# MCU.net
KiCad netlist of a schematic drawn in Altium Designer
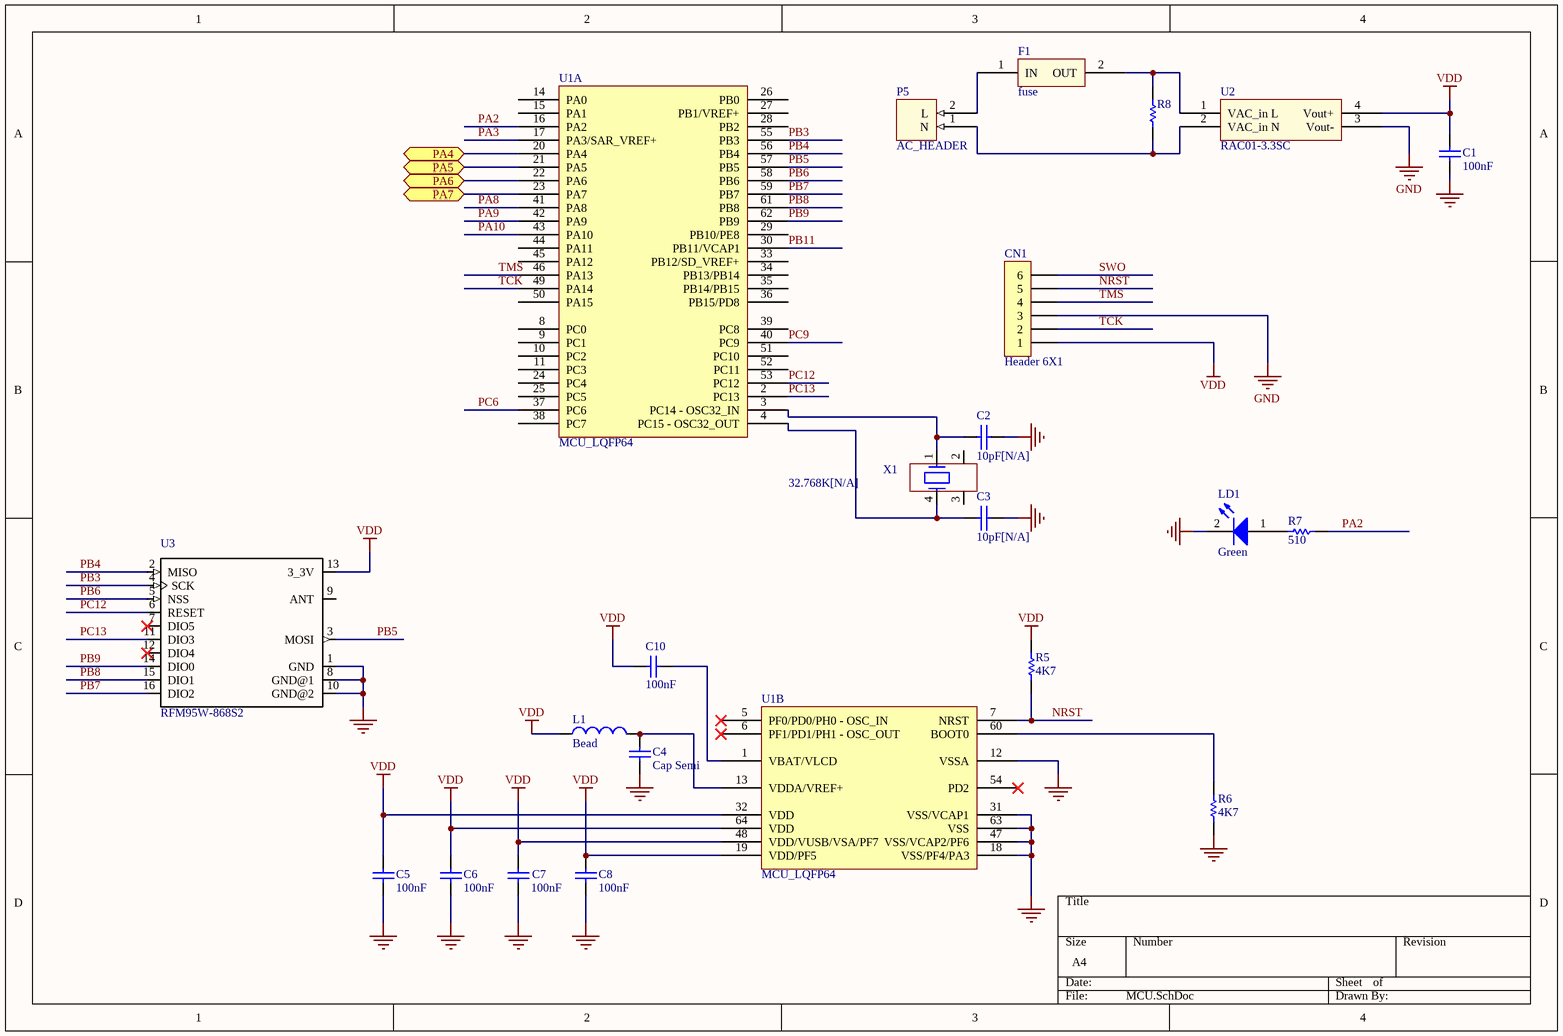
[diagram p0: MCU.SchDoc]

(export (version "E")
  (design (tool "Eeschema 10.0.6"))
  (components
    (comp (ref "C1")
      (value "100nF")
      (footprint "0603C")
      (description "Capacitor")
      (fields (field (name "MANUFACTURER") "AVX Corporation") (field (name "PUBLISHER") "Altium Limited"))
      (libsource (lib "Miscellaneous Devices") (part "Cap"))
    )
    (comp (ref "C2")
      (value "10pF[N/A]")
      (footprint "0603C")
      (description "Capacitor")
      (fields (field (name "MANUFACTURER") "Murata Electronics North America"))
      (libsource (lib "MB1136") (part "CAP"))
    )
    (comp (ref "C3")
      (value "10pF[N/A]")
      (footprint "0603C")
      (description "Capacitor")
      (fields (field (name "MANUFACTURER") "Murata Electronics North America"))
      (libsource (lib "*") (part "CAP"))
    )
    (comp (ref "C4")
      (value "Cap Semi")
      (footprint "1608[0603]")
      (description "Capacitor (Semiconductor SIM Model)")
      (fields (field (name "MANUFACTURER") "TDK") (field (name "PUBLISHER") "Altium Limited"))
      (libsource (lib "Miscellaneous Devices") (part "Cap Semi"))
    )
    (comp (ref "C5")
      (value "100nF")
      (footprint "0603C")
      (description "Capacitor")
      (fields (field (name "MANUFACTURER") "TDK") (field (name "PUBLISHER") "Altium Limited"))
      (libsource (lib "Miscellaneous Devices") (part "Cap"))
    )
    (comp (ref "C6")
      (value "100nF")
      (footprint "0603C")
      (description "Capacitor")
      (fields (field (name "MANUFACTURER") "TDK") (field (name "PUBLISHER") "Altium Limited"))
      (libsource (lib "Miscellaneous Devices") (part "Cap"))
    )
    (comp (ref "C7")
      (value "100nF")
      (footprint "0603C")
      (description "Capacitor")
      (fields (field (name "MANUFACTURER") "TDK") (field (name "PUBLISHER") "Altium Limited"))
      (libsource (lib "Miscellaneous Devices") (part "Cap"))
    )
    (comp (ref "C8")
      (value "100nF")
      (footprint "0603C")
      (description "Capacitor")
      (fields (field (name "MANUFACTURER") "TDK") (field (name "PUBLISHER") "Altium Limited"))
      (libsource (lib "Miscellaneous Devices") (part "Cap"))
    )
    (comp (ref "C10")
      (value "100nF")
      (footprint "0603C")
      (description "Capacitor")
      (fields (field (name "MANUFACTURER") "AVX Corporation") (field (name "PUBLISHER") "Altium Limited"))
      (libsource (lib "Miscellaneous Devices") (part "Cap"))
    )
    (comp (ref "CN1")
      (value "Header 6X1")
      (footprint "1*6P")
      (description "Header, 6-Pin, Single row")
      (fields (field (name "MANUFACTURER") "Molex") (field (name "PUBLISHER") "Altium Limited"))
      (libsource (lib "MB1136") (part "Header 6X1"))
    )
    (comp (ref "F1")
      (value "fuse")
      (footprint "fuse")
      (description "240VAC 1A")
      (fields (field (name "MANUFACTURER") "Bel Fuse Inc."))
      (libsource (lib "seeds") (part "fuse"))
    )
    (comp (ref "L1")
      (value "Bead")
      (footprint "INDC1608L")
      (description "Inductor")
      (fields (field (name "MANUFACTURER") "Taiyo Yuden") (field (name "PUBLISHER") "Altium Limited"))
      (libsource (lib "Miscellaneous Devices") (part "Inductor"))
    )
    (comp (ref "LD1")
      (value "Green")
      (footprint "0603D")
      (description "Typical RED, GREEN, YELLOW, AMBER GaAs LED")
      (fields (field (name "MANUFACTURER") "Lite-On") (field (name "PUBLISHER") "Altium Limited"))
      (libsource (lib "Miscellaneous Devices") (part "LED2"))
    )
    (comp (ref "P5")
      (value "AC_HEADER")
      (footprint "ac_header_2")
      (fields (field (name "MANUFACTURER") "On Shore Technology"))
      (libsource (lib "seeds") (part "AC_HEADER"))
    )
    (comp (ref "R5")
      (value "4K7")
      (footprint "0603R")
      (description "Resistor")
      (fields (field (name "MANUFACTURER") "Yageo") (field (name "PUBLISHER") "Altium Limited"))
      (libsource (lib "MB1136") (part "Res1"))
    )
    (comp (ref "R6")
      (value "4K7")
      (footprint "0603R")
      (description "Resistor")
      (fields (field (name "MANUFACTURER") "Yageo") (field (name "PUBLISHER") "Altium Limited"))
      (libsource (lib "MB1136") (part "Res1"))
    )
    (comp (ref "R7")
      (value "510")
      (footprint "0603R")
      (description "Resistor")
      (fields (field (name "MANUFACTURER") "Rohm Semiconductor") (field (name "PUBLISHER") "Altium Limited"))
      (libsource (lib "Miscellaneous Devices") (part "Res1"))
    )
    (comp (ref "R8")
      (value "~")
      (footprint "varistor")
      (description "Resistor")
      (fields (field (name "MANUFACTURER") "Epcos (TDK)") (field (name "PUBLISHER") "Altium Limited"))
      (libsource (lib "MB1136") (part "Res1"))
    )
    (comp (ref "U1")
      (value "MCU_LQFP64")
      (footprint "LQFP64")
      (fields (field (name "MANUFACTURER") "STM"))
      (libsource (lib "MB1136") (part "MCU_LQFP64"))
    )
    (comp (ref "U2")
      (value "RAC01-3.3SC")
      (footprint "RAC01-3.3SC")
      (description "AC/DC converter")
      (fields (field (name "MANUFACTURER") "Recom Power"))
      (libsource (lib "seeds") (part "RAC01-3.3SC"))
    )
    (comp (ref "U3")
      (value "RFM95W-868S2")
      (footprint "XCVR_RFM95W-868S2")
      (fields (field (name "MF") "Hope Microelectronics") (field (name "MANUFACTURER") "RF Solutions"))
      (libsource (lib "RFM95W-868S2") (part "RFM95W-868S2"))
    )
    (comp (ref "X1") (value "32.768K[N/A]") (footprint "XTAL_4SM_8X3R8") (libsource (lib "*") (part "MC306")))
  )
  (nets
    (net (code "1") (name "/NRST") (class "Default")
      (node (ref "CN1") (pin "5") (pinfunction "5_5") (pintype "passive"))
      (node (ref "R5") (pin "1") (pinfunction "1_1") (pintype "passive"))
      (node (ref "U1") (pin "7") (pinfunction "NRST_7") (pintype "passive"))
    )
    (net (code "2") (name "/PA2") (class "Default")
      (node (ref "R7") (pin "1") (pinfunction "1_1") (pintype "passive"))
      (node (ref "U1") (pin "16") (pinfunction "PA2_16") (pintype "passive"))
    )
    (net (code "3") (name "/PA3") (class "Default")
      (node (ref "U1") (pin "17") (pinfunction "PA3/SAR_VREF+_17") (pintype "passive"))
    )
    (net (code "4") (name "/PA4") (class "Default")
      (node (ref "U1") (pin "20") (pinfunction "PA4_20") (pintype "passive"))
    )
    (net (code "5") (name "/PA5") (class "Default")
      (node (ref "U1") (pin "21") (pinfunction "PA5_21") (pintype "passive"))
    )
    (net (code "6") (name "/PA6") (class "Default")
      (node (ref "U1") (pin "22") (pinfunction "PA6_22") (pintype "passive"))
    )
    (net (code "7") (name "/PA7") (class "Default")
      (node (ref "U1") (pin "23") (pinfunction "PA7_23") (pintype "passive"))
    )
    (net (code "8") (name "/PA8") (class "Default")
      (node (ref "U1") (pin "41") (pinfunction "PA8_41") (pintype "passive"))
    )
    (net (code "9") (name "/PA9") (class "Default")
      (node (ref "U1") (pin "42") (pinfunction "PA9_42") (pintype "passive"))
    )
    (net (code "10") (name "/PA10") (class "Default")
      (node (ref "U1") (pin "43") (pinfunction "PA10_43") (pintype "passive"))
    )
    (net (code "11") (name "/PB3") (class "Default")
      (node (ref "U1") (pin "55") (pinfunction "PB3_55") (pintype "passive"))
      (node (ref "U3") (pin "4") (pinfunction "SCK_4") (pintype "input"))
    )
    (net (code "12") (name "/PB4") (class "Default")
      (node (ref "U1") (pin "56") (pinfunction "PB4_56") (pintype "passive"))
      (node (ref "U3") (pin "2") (pinfunction "MISO_2") (pintype "input"))
    )
    (net (code "13") (name "/PB5") (class "Default")
      (node (ref "U1") (pin "57") (pinfunction "PB5_57") (pintype "passive"))
      (node (ref "U3") (pin "3") (pinfunction "MOSI_3") (pintype "output"))
    )
    (net (code "14") (name "/PB6") (class "Default")
      (node (ref "U1") (pin "58") (pinfunction "PB6_58") (pintype "passive"))
      (node (ref "U3") (pin "5") (pinfunction "NSS_5") (pintype "input"))
    )
    (net (code "15") (name "/PB7") (class "Default")
      (node (ref "U1") (pin "59") (pinfunction "PB7_59") (pintype "passive"))
      (node (ref "U3") (pin "16") (pinfunction "DIO2_16") (pintype "bidirectional"))
    )
    (net (code "16") (name "/PB8") (class "Default")
      (node (ref "U1") (pin "61") (pinfunction "PB8_61") (pintype "passive"))
      (node (ref "U3") (pin "15") (pinfunction "DIO1_15") (pintype "bidirectional"))
    )
    (net (code "17") (name "/PB9") (class "Default")
      (node (ref "U1") (pin "62") (pinfunction "PB9_62") (pintype "passive"))
      (node (ref "U3") (pin "14") (pinfunction "DIO0_14") (pintype "bidirectional"))
    )
    (net (code "18") (name "/PB11") (class "Default")
      (node (ref "U1") (pin "30") (pinfunction "PB11/VCAP1_30") (pintype "passive"))
    )
    (net (code "19") (name "/PC6") (class "Default")
      (node (ref "U1") (pin "37") (pinfunction "PC6_37") (pintype "passive"))
    )
    (net (code "20") (name "/PC9") (class "Default")
      (node (ref "U1") (pin "40") (pinfunction "PC9_40") (pintype "passive"))
    )
    (net (code "21") (name "/PC12") (class "Default")
      (node (ref "U1") (pin "53") (pinfunction "PC12_53") (pintype "passive"))
      (node (ref "U3") (pin "6") (pinfunction "RESET_6") (pintype "bidirectional"))
    )
    (net (code "22") (name "/PC13") (class "Default")
      (node (ref "U1") (pin "2") (pinfunction "PC13_2") (pintype "passive"))
      (node (ref "U3") (pin "11") (pinfunction "DIO3_11") (pintype "bidirectional"))
    )
    (net (code "23") (name "/SWO") (class "Default")
      (node (ref "CN1") (pin "6") (pinfunction "6_6") (pintype "passive"))
    )
    (net (code "24") (name "/TCK") (class "Default")
      (node (ref "CN1") (pin "2") (pinfunction "2_2") (pintype "passive"))
      (node (ref "U1") (pin "49") (pinfunction "PA14_49") (pintype "passive"))
    )
    (net (code "25") (name "/TMS") (class "Default")
      (node (ref "CN1") (pin "4") (pinfunction "4_4") (pintype "passive"))
      (node (ref "U1") (pin "46") (pinfunction "PA13_46") (pintype "passive"))
    )
    (net (code "26") (name "GND") (class "Default")
      (node (ref "C1") (pin "2") (pinfunction "2_2") (pintype "passive"))
      (node (ref "C2") (pin "2") (pinfunction "2_2") (pintype "passive"))
      (node (ref "C3") (pin "2") (pinfunction "2_2") (pintype "passive"))
      (node (ref "C4") (pin "2") (pinfunction "2_2") (pintype "passive"))
      (node (ref "C5") (pin "2") (pinfunction "2_2") (pintype "passive"))
      (node (ref "C6") (pin "2") (pinfunction "2_2") (pintype "passive"))
      (node (ref "C7") (pin "2") (pinfunction "2_2") (pintype "passive"))
      (node (ref "C8") (pin "2") (pinfunction "2_2") (pintype "passive"))
      (node (ref "CN1") (pin "3") (pinfunction "3_3") (pintype "passive"))
      (node (ref "LD1") (pin "2") (pinfunction "K_2") (pintype "passive"))
      (node (ref "R6") (pin "1") (pinfunction "1_1") (pintype "passive"))
      (node (ref "U1") (pin "12") (pinfunction "VSSA_12") (pintype "passive"))
      (node (ref "U1") (pin "18") (pinfunction "VSS/PF4/PA3_18") (pintype "passive"))
      (node (ref "U1") (pin "31") (pinfunction "VSS/VCAP1_31") (pintype "passive"))
      (node (ref "U1") (pin "47") (pinfunction "VSS/VCAP2/PF6_47") (pintype "passive"))
      (node (ref "U1") (pin "63") (pinfunction "VSS_63") (pintype "passive"))
      (node (ref "U2") (pin "3") (pinfunction "Vout-_3") (pintype "power_in"))
      (node (ref "U3") (pin "1") (pinfunction "GND_1") (pintype "power_in"))
      (node (ref "U3") (pin "10") (pinfunction "GND@2_10") (pintype "power_in"))
      (node (ref "U3") (pin "8") (pinfunction "GND@1_8") (pintype "power_in"))
    )
    (net (code "27") (name "Net-(F1-IN)") (class "Default")
      (node (ref "F1") (pin "1") (pinfunction "IN_1") (pintype "passive"))
      (node (ref "P5") (pin "2") (pinfunction "L_2") (pintype "input"))
    )
    (net (code "28") (name "Net-(F1-OUT)") (class "Default")
      (node (ref "F1") (pin "2") (pinfunction "OUT_2") (pintype "passive"))
      (node (ref "R8") (pin "2") (pinfunction "2_2") (pintype "passive"))
      (node (ref "U2") (pin "1") (pinfunction "VAC_in_L_1") (pintype "power_in"))
    )
    (net (code "29") (name "Net-(LD1-A)") (class "Default")
      (node (ref "LD1") (pin "1") (pinfunction "A_1") (pintype "passive"))
      (node (ref "R7") (pin "2") (pinfunction "2_2") (pintype "passive"))
    )
    (net (code "30") (name "Net-(P5-N)") (class "Default")
      (node (ref "P5") (pin "1") (pinfunction "N_1") (pintype "input"))
      (node (ref "R8") (pin "1") (pinfunction "1_1") (pintype "passive"))
      (node (ref "U2") (pin "2") (pinfunction "VAC_in_N_2") (pintype "power_in"))
    )
    (net (code "31") (name "Net-(U1A-PC14_-_OSC32_IN)") (class "Default")
      (node (ref "C2") (pin "1") (pinfunction "1_1") (pintype "passive"))
      (node (ref "U1") (pin "3") (pinfunction "PC14_-_OSC32_IN_3") (pintype "passive"))
      (node (ref "X1") (pin "1") (pinfunction "1_1") (pintype "passive"))
    )
    (net (code "32") (name "Net-(U1A-PC15_-_OSC32_OUT)") (class "Default")
      (node (ref "C3") (pin "1") (pinfunction "1_1") (pintype "passive"))
      (node (ref "U1") (pin "4") (pinfunction "PC15_-_OSC32_OUT_4") (pintype "passive"))
      (node (ref "X1") (pin "4") (pinfunction "4_4") (pintype "passive"))
    )
    (net (code "33") (name "Net-(U1B-BOOT0)") (class "Default")
      (node (ref "R6") (pin "2") (pinfunction "2_2") (pintype "passive"))
      (node (ref "U1") (pin "60") (pinfunction "BOOT0_60") (pintype "passive"))
    )
    (net (code "34") (name "Net-(U1B-VBAT{slash}VLCD)") (class "Default")
      (node (ref "C10") (pin "2") (pinfunction "2_2") (pintype "passive"))
      (node (ref "U1") (pin "1") (pinfunction "VBAT/VLCD_1") (pintype "passive"))
    )
    (net (code "35") (name "Net-(U1B-VDDA{slash}VREF+)") (class "Default")
      (node (ref "C4") (pin "1") (pinfunction "1_1") (pintype "passive"))
      (node (ref "L1") (pin "2") (pinfunction "2_2") (pintype "passive"))
      (node (ref "U1") (pin "13") (pinfunction "VDDA/VREF+_13") (pintype "passive"))
    )
    (net (code "36") (name "VDD") (class "Default")
      (node (ref "C1") (pin "1") (pinfunction "1_1") (pintype "passive"))
      (node (ref "C10") (pin "1") (pinfunction "1_1") (pintype "passive"))
      (node (ref "C5") (pin "1") (pinfunction "1_1") (pintype "passive"))
      (node (ref "C6") (pin "1") (pinfunction "1_1") (pintype "passive"))
      (node (ref "C7") (pin "1") (pinfunction "1_1") (pintype "passive"))
      (node (ref "C8") (pin "1") (pinfunction "1_1") (pintype "passive"))
      (node (ref "CN1") (pin "1") (pinfunction "1_1") (pintype "passive"))
      (node (ref "L1") (pin "1") (pinfunction "1_1") (pintype "passive"))
      (node (ref "R5") (pin "2") (pinfunction "2_2") (pintype "passive"))
      (node (ref "U1") (pin "19") (pinfunction "VDD/PF5_19") (pintype "passive"))
      (node (ref "U1") (pin "32") (pinfunction "VDD_32") (pintype "passive"))
      (node (ref "U1") (pin "48") (pinfunction "VDD/VUSB/VSA/PF7_48") (pintype "passive"))
      (node (ref "U1") (pin "64") (pinfunction "VDD_64") (pintype "passive"))
      (node (ref "U2") (pin "4") (pinfunction "Vout+_4") (pintype "power_in"))
      (node (ref "U3") (pin "13") (pinfunction "3_3V_13") (pintype "power_in"))
    )
    (net (code "37") (name "unconnected-(U1A-PA0-Pad14)") (class "Default")
      (node (ref "U1") (pin "14") (pinfunction "PA0_14") (pintype "passive"))
    )
    (net (code "38") (name "unconnected-(U1A-PA1-Pad15)") (class "Default")
      (node (ref "U1") (pin "15") (pinfunction "PA1_15") (pintype "passive"))
    )
    (net (code "39") (name "unconnected-(U1A-PA11-Pad44)") (class "Default")
      (node (ref "U1") (pin "44") (pinfunction "PA11_44") (pintype "passive"))
    )
    (net (code "40") (name "unconnected-(U1A-PA12-Pad45)") (class "Default")
      (node (ref "U1") (pin "45") (pinfunction "PA12_45") (pintype "passive"))
    )
    (net (code "41") (name "unconnected-(U1A-PA15-Pad50)") (class "Default")
      (node (ref "U1") (pin "50") (pinfunction "PA15_50") (pintype "passive"))
    )
    (net (code "42") (name "unconnected-(U1A-PB0-Pad26)") (class "Default")
      (node (ref "U1") (pin "26") (pinfunction "PB0_26") (pintype "passive"))
    )
    (net (code "43") (name "unconnected-(U1A-PB1{slash}VREF+-Pad27)") (class "Default")
      (node (ref "U1") (pin "27") (pinfunction "PB1/VREF+_27") (pintype "passive"))
    )
    (net (code "44") (name "unconnected-(U1A-PB2-Pad28)") (class "Default")
      (node (ref "U1") (pin "28") (pinfunction "PB2_28") (pintype "passive"))
    )
    (net (code "45") (name "unconnected-(U1A-PB10{slash}PE8-Pad29)") (class "Default")
      (node (ref "U1") (pin "29") (pinfunction "PB10/PE8_29") (pintype "passive"))
    )
    (net (code "46") (name "unconnected-(U1A-PB12{slash}SD_VREF+-Pad33)") (class "Default")
      (node (ref "U1") (pin "33") (pinfunction "PB12/SD_VREF+_33") (pintype "passive"))
    )
    (net (code "47") (name "unconnected-(U1A-PB13{slash}PB14-Pad34)") (class "Default")
      (node (ref "U1") (pin "34") (pinfunction "PB13/PB14_34") (pintype "passive"))
    )
    (net (code "48") (name "unconnected-(U1A-PB14{slash}PB15-Pad35)") (class "Default")
      (node (ref "U1") (pin "35") (pinfunction "PB14/PB15_35") (pintype "passive"))
    )
    (net (code "49") (name "unconnected-(U1A-PB15{slash}PD8-Pad36)") (class "Default")
      (node (ref "U1") (pin "36") (pinfunction "PB15/PD8_36") (pintype "passive"))
    )
    (net (code "50") (name "unconnected-(U1A-PC0-Pad8)") (class "Default")
      (node (ref "U1") (pin "8") (pinfunction "PC0_8") (pintype "passive"))
    )
    (net (code "51") (name "unconnected-(U1A-PC1-Pad9)") (class "Default")
      (node (ref "U1") (pin "9") (pinfunction "PC1_9") (pintype "passive"))
    )
    (net (code "52") (name "unconnected-(U1A-PC2-Pad10)") (class "Default")
      (node (ref "U1") (pin "10") (pinfunction "PC2_10") (pintype "passive"))
    )
    (net (code "53") (name "unconnected-(U1A-PC3-Pad11)") (class "Default")
      (node (ref "U1") (pin "11") (pinfunction "PC3_11") (pintype "passive"))
    )
    (net (code "54") (name "unconnected-(U1A-PC4-Pad24)") (class "Default")
      (node (ref "U1") (pin "24") (pinfunction "PC4_24") (pintype "passive"))
    )
    (net (code "55") (name "unconnected-(U1A-PC5-Pad25)") (class "Default")
      (node (ref "U1") (pin "25") (pinfunction "PC5_25") (pintype "passive"))
    )
    (net (code "56") (name "unconnected-(U1A-PC7-Pad38)") (class "Default")
      (node (ref "U1") (pin "38") (pinfunction "PC7_38") (pintype "passive"))
    )
    (net (code "57") (name "unconnected-(U1A-PC8-Pad39)") (class "Default")
      (node (ref "U1") (pin "39") (pinfunction "PC8_39") (pintype "passive"))
    )
    (net (code "58") (name "unconnected-(U1A-PC10-Pad51)") (class "Default")
      (node (ref "U1") (pin "51") (pinfunction "PC10_51") (pintype "passive"))
    )
    (net (code "59") (name "unconnected-(U1A-PC11-Pad52)") (class "Default")
      (node (ref "U1") (pin "52") (pinfunction "PC11_52") (pintype "passive"))
    )
    (net (code "60") (name "unconnected-(U1B-PD2-Pad54)") (class "Default")
      (node (ref "U1") (pin "54") (pinfunction "PD2_54") (pintype "passive+no_connect"))
    )
    (net (code "61") (name "unconnected-(U1B-PF0{slash}PD0{slash}PH0_-_OSC_IN-Pad5)") (class "Default")
      (node (ref "U1") (pin "5") (pinfunction "PF0/PD0/PH0_-_OSC_IN_5") (pintype "passive+no_connect"))
    )
    (net (code "62") (name "unconnected-(U1B-PF1{slash}PD1{slash}PH1_-_OSC_OUT-Pad6)") (class "Default")
      (node (ref "U1") (pin "6") (pinfunction "PF1/PD1/PH1_-_OSC_OUT_6") (pintype "passive+no_connect"))
    )
    (net (code "63") (name "unconnected-(U3-ANT-Pad9)") (class "Default")
      (node (ref "U3") (pin "9") (pinfunction "ANT_9") (pintype "passive"))
    )
    (net (code "64") (name "unconnected-(U3-DIO4-Pad12)") (class "Default")
      (node (ref "U3") (pin "12") (pinfunction "DIO4_12") (pintype "bidirectional+no_connect"))
    )
    (net (code "65") (name "unconnected-(U3-DIO5-Pad7)") (class "Default")
      (node (ref "U3") (pin "7") (pinfunction "DIO5_7") (pintype "bidirectional+no_connect"))
    )
    (net (code "66") (name "unconnected-(X1-Pad2)") (class "Default")
      (node (ref "X1") (pin "2") (pinfunction "2_2") (pintype "passive"))
    )
    (net (code "67") (name "unconnected-(X1-Pad3)") (class "Default")
      (node (ref "X1") (pin "3") (pinfunction "3_3") (pintype "passive"))
    )
  )
)
